# design.net
KiCad netlist of a schematic drawn in Altium Designer
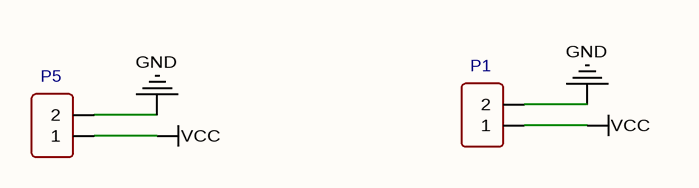
[diagram p0: 车架.schdoc]

(export (version "E")
  (design (tool "Eeschema 10.0.6"))
  (components
    (comp (ref "P1")
      (value "Header-Female-2.54_1x2")
      (fields
        (field (name "BOM_MANUFACTURER PART") "2.54-1*2PFemale")
        (field (name "BOM_SUPPLIER PART") "C49661")
      )
      (libsource (lib "altium-import") (part "root_2_Header-Female-2.54_1x2_"))
    )
    (comp (ref "P5")
      (value "Header-Female-2.54_1x2")
      (fields
        (field (name "BOM_MANUFACTURER PART") "2.54-1*2PFemale")
        (field (name "BOM_SUPPLIER PART") "C49661")
      )
      (libsource (lib "altium-import") (part "root_2_Header-Female-2.54_1x2_"))
    )
  )
  (nets
    (net (code "1") (name "GND") (class "Default")
      (node (ref "P1") (pin "2") (pinfunction "2_2") (pintype "passive"))
      (node (ref "P5") (pin "2") (pinfunction "2_2") (pintype "passive"))
    )
    (net (code "2") (name "VCC") (class "Default")
      (node (ref "P1") (pin "1") (pinfunction "1_1") (pintype "passive"))
      (node (ref "P5") (pin "1") (pinfunction "1_1") (pintype "passive"))
    )
  )
)
